# BlueNRG.net
KiCad netlist of a schematic drawn in EAGLE
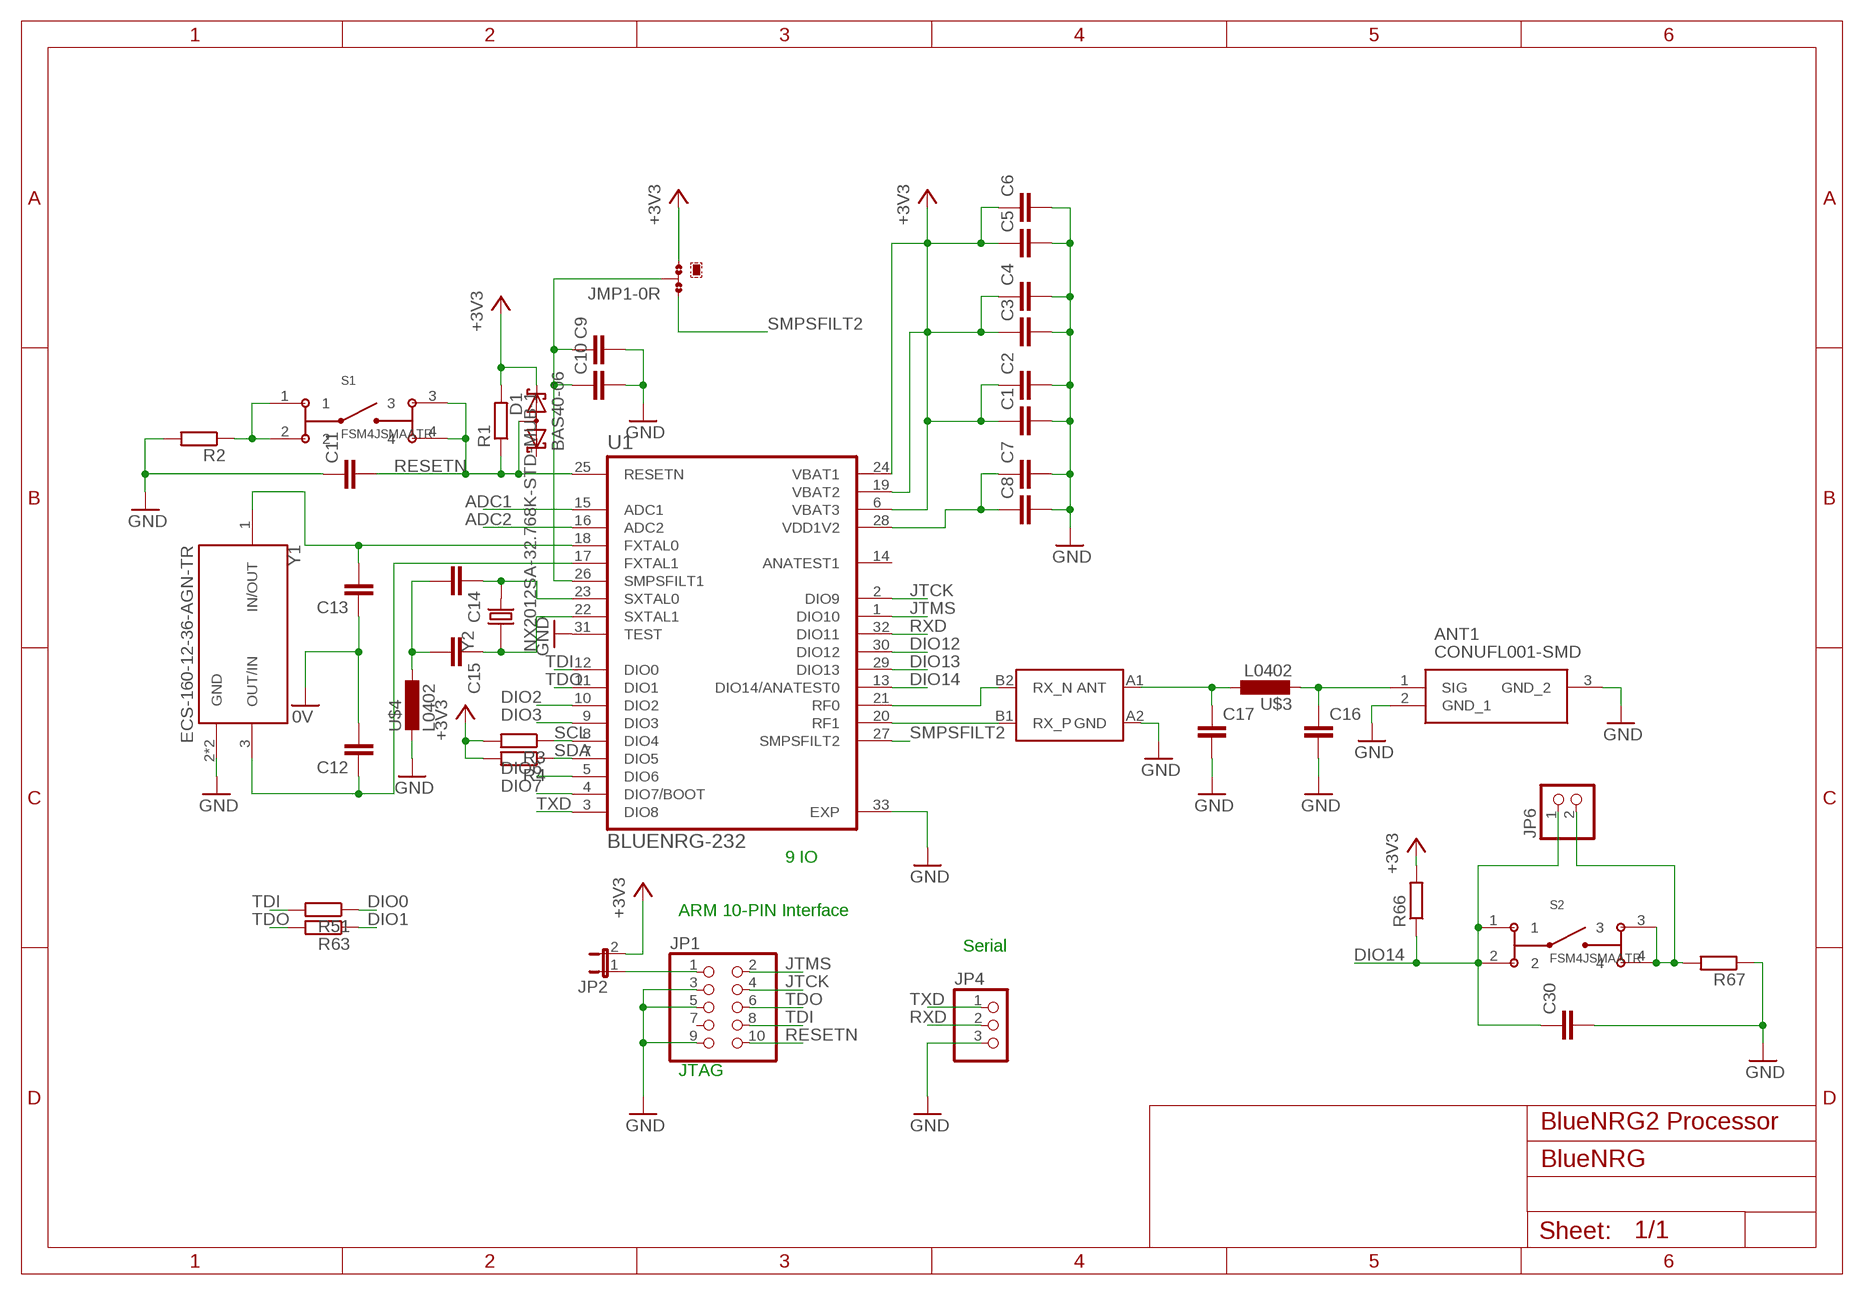
[diagram p0: schematic, sheet 1]

(export (version "E")
  (design (tool "Eeschema 10.0.6"))
  (components
    (comp (ref "ANT1")
      (value "CONUFL001-SMD")
      (footprint "eagle-import:CONUFL001-SMD")
      (fields (field (name "MOUSER_PART_NUMBER") "712-CONUFL001-SMD"))
      (libsource (lib "eagle-import") (part "CONUFL001-SMD"))
    )
    (comp (ref "C1")
      (value "C-EUC0805K")
      (footprint "eagle-import:C0805K")
      (libsource (lib "eagle-import") (part "C-EUC0805K"))
    )
    (comp (ref "C2")
      (value "C-EUC0805K")
      (footprint "eagle-import:C0805K")
      (libsource (lib "eagle-import") (part "C-EUC0805K"))
    )
    (comp (ref "C3")
      (value "C-EUC0805K")
      (footprint "eagle-import:C0805K")
      (libsource (lib "eagle-import") (part "C-EUC0805K"))
    )
    (comp (ref "C4")
      (value "C-EUC0805K")
      (footprint "eagle-import:C0805K")
      (libsource (lib "eagle-import") (part "C-EUC0805K"))
    )
    (comp (ref "C5")
      (value "C-EUC0805K")
      (footprint "eagle-import:C0805K")
      (libsource (lib "eagle-import") (part "C-EUC0805K"))
    )
    (comp (ref "C6")
      (value "C-EUC0805K")
      (footprint "eagle-import:C0805K")
      (libsource (lib "eagle-import") (part "C-EUC0805K"))
    )
    (comp (ref "C7")
      (value "C-EUC0805K")
      (footprint "eagle-import:C0805K")
      (libsource (lib "eagle-import") (part "C-EUC0805K"))
    )
    (comp (ref "C8")
      (value "C-EUC0805K")
      (footprint "eagle-import:C0805K")
      (libsource (lib "eagle-import") (part "C-EUC0805K"))
    )
    (comp (ref "C9")
      (value "C-EUC0805K")
      (footprint "eagle-import:C0805K")
      (libsource (lib "eagle-import") (part "C-EUC0805K"))
    )
    (comp (ref "C10")
      (value "C-EUC0805K")
      (footprint "eagle-import:C0805K")
      (libsource (lib "eagle-import") (part "C-EUC0805K"))
    )
    (comp (ref "C11")
      (value "C-EUC0805")
      (footprint "eagle-import:C0805")
      (libsource (lib "eagle-import") (part "C-EUC0805"))
    )
    (comp (ref "C12")
      (value "C-EUC0805")
      (footprint "eagle-import:C0805")
      (libsource (lib "eagle-import") (part "C-EUC0805"))
    )
    (comp (ref "C13")
      (value "C-EUC0805")
      (footprint "eagle-import:C0805")
      (libsource (lib "eagle-import") (part "C-EUC0805"))
    )
    (comp (ref "C14")
      (value "C-EUC0805")
      (footprint "eagle-import:C0805")
      (libsource (lib "eagle-import") (part "C-EUC0805"))
    )
    (comp (ref "C15")
      (value "C-EUC0805")
      (footprint "eagle-import:C0805")
      (libsource (lib "eagle-import") (part "C-EUC0805"))
    )
    (comp (ref "C16")
      (value "C-EUC0402")
      (footprint "eagle-import:C0402")
      (libsource (lib "eagle-import") (part "C-EUC0402"))
    )
    (comp (ref "C17")
      (value "C-EUC0402")
      (footprint "eagle-import:C0402")
      (libsource (lib "eagle-import") (part "C-EUC0402"))
    )
    (comp (ref "C30")
      (value "C-EUC0805")
      (footprint "eagle-import:C0805")
      (libsource (lib "eagle-import") (part "C-EUC0805"))
    )
    (comp (ref "D1")
      (value "BAS40-06")
      (footprint "eagle-import:SOT23")
      (libsource (lib "eagle-import") (part "BAS40-06"))
    )
    (comp (ref "JMP1")
      (value "0R-JUMPA")
      (footprint "eagle-import:A0R-JMP")
      (libsource (lib "eagle-import") (part "0R-JUMPA"))
    )
    (comp (ref "JP1")
      (value "PINHD-2X5")
      (footprint "eagle-import:2X05")
      (libsource (lib "eagle-import") (part "PINHD-2X5"))
    )
    (comp (ref "JP2")
      (value "JP1E")
      (footprint "eagle-import:JP1")
      (libsource (lib "eagle-import") (part "JP1E"))
    )
    (comp (ref "JP4")
      (value "PINHD-1X3")
      (footprint "eagle-import:1X03")
      (libsource (lib "eagle-import") (part "PINHD-1X3"))
    )
    (comp (ref "JP6")
      (value "PINHD-1X2")
      (footprint "eagle-import:1X02")
      (libsource (lib "eagle-import") (part "PINHD-1X2"))
    )
    (comp (ref "R1")
      (value "R-EU_R0805")
      (footprint "eagle-import:R0805")
      (libsource (lib "eagle-import") (part "R-EU_R0805"))
    )
    (comp (ref "R2")
      (value "R-EU_R0805")
      (footprint "eagle-import:R0805")
      (libsource (lib "eagle-import") (part "R-EU_R0805"))
    )
    (comp (ref "R3")
      (value "R-EU_R0805")
      (footprint "eagle-import:R0805")
      (libsource (lib "eagle-import") (part "R-EU_R0805"))
    )
    (comp (ref "R4")
      (value "R-EU_R0805")
      (footprint "eagle-import:R0805")
      (libsource (lib "eagle-import") (part "R-EU_R0805"))
    )
    (comp (ref "R51")
      (value "R-EU_R0805")
      (footprint "eagle-import:R0805")
      (libsource (lib "eagle-import") (part "R-EU_R0805"))
    )
    (comp (ref "R63")
      (value "R-EU_R0805")
      (footprint "eagle-import:R0805")
      (libsource (lib "eagle-import") (part "R-EU_R0805"))
    )
    (comp (ref "R66")
      (value "R-EU_R1210")
      (footprint "eagle-import:R1210")
      (libsource (lib "eagle-import") (part "R-EU_R1210"))
    )
    (comp (ref "R67")
      (value "R-EU_R1210")
      (footprint "eagle-import:R1210")
      (libsource (lib "eagle-import") (part "R-EU_R1210"))
    )
    (comp (ref "S1")
      (value "FSM4JSMAATR")
      (footprint "eagle-import:SW_FSM4JSMAATR")
      (fields (field (name "MF") "TE Connectivity"))
      (libsource (lib "eagle-import") (part "FSM4JSMAATR"))
    )
    (comp (ref "S2")
      (value "FSM4JSMAATR")
      (footprint "eagle-import:SW_FSM4JSMAATR")
      (fields (field (name "MF") "TE Connectivity"))
      (libsource (lib "eagle-import") (part "FSM4JSMAATR"))
    )
    (comp (ref "U$3")
      (value "L0402")
      (footprint "eagle-import:R0402")
      (libsource (lib "eagle-import") (part "L0402"))
    )
    (comp (ref "U$4")
      (value "L0402")
      (footprint "eagle-import:R0402")
      (libsource (lib "eagle-import") (part "L0402"))
    )
    (comp (ref "U$5")
      (value "BALF-NRG-01D3")
      (footprint "eagle-import:FLIPCHIP")
      (fields (field (name "MF") "STMicroelectronics"))
      (libsource (lib "eagle-import") (part "BALF-NRG-01D3"))
    )
    (comp (ref "U1")
      (value "BLUENRG-232")
      (footprint "eagle-import:QFN50P500X500X100-33T345N")
      (fields (field (name "MF") "STMicroelectronics"))
      (libsource (lib "eagle-import") (part "BLUENRG-232"))
    )
    (comp (ref "Y1")
      (value "ECS-160-12-36-AGN-TR")
      (footprint "eagle-import:XTAL_ECS-160-12-36-AGN-TR")
      (fields (field (name "MF") "ECS Inc."))
      (libsource (lib "eagle-import") (part "ECS-160-12-36-AGN-TR"))
    )
    (comp (ref "Y2")
      (value "NX2012SA-32.768K-STD-MUB-1")
      (footprint "eagle-import:XTAL_NX2012SA-32.768K-STD-MUB-1")
      (fields (field (name "MF") "NDK America,"))
      (libsource (lib "eagle-import") (part "NX2012SA-32.768K-STD-MUB-1"))
    )
  )
  (nets
    (net (code "1") (name "+3V3") (class "Default")
      (node (ref "C1") (pin "1") (pinfunction "1_1") (pintype "passive"))
      (node (ref "C2") (pin "1") (pinfunction "1_1") (pintype "passive"))
      (node (ref "C3") (pin "1") (pinfunction "1_1") (pintype "passive"))
      (node (ref "C4") (pin "1") (pinfunction "1_1") (pintype "passive"))
      (node (ref "C5") (pin "1") (pinfunction "1_1") (pintype "passive"))
      (node (ref "C6") (pin "1") (pinfunction "1_1") (pintype "passive"))
      (node (ref "D1") (pin "2") (pinfunction "K2_2") (pintype "passive"))
      (node (ref "JMP1") (pin "3") (pinfunction "3_3") (pintype "passive"))
      (node (ref "JP2") (pin "2") (pinfunction "2_2") (pintype "passive"))
      (node (ref "R1") (pin "2") (pinfunction "2_2") (pintype "passive"))
      (node (ref "R3") (pin "2") (pinfunction "2_2") (pintype "passive"))
      (node (ref "R4") (pin "2") (pinfunction "2_2") (pintype "passive"))
      (node (ref "R66") (pin "2") (pinfunction "2_2") (pintype "passive"))
      (node (ref "U1") (pin "19") (pinfunction "VBAT2_19") (pintype "power_in"))
      (node (ref "U1") (pin "24") (pinfunction "VBAT1_24") (pintype "power_in"))
      (node (ref "U1") (pin "6") (pinfunction "VBAT3_6") (pintype "power_in"))
    )
    (net (code "2") (name "/ADC1") (class "Default")
      (node (ref "U1") (pin "15") (pinfunction "ADC1_15") (pintype "input"))
    )
    (net (code "3") (name "/ADC2") (class "Default")
      (node (ref "U1") (pin "16") (pinfunction "ADC2_16") (pintype "input"))
    )
    (net (code "4") (name "/DIO0") (class "Default")
      (node (ref "R51") (pin "1") (pinfunction "1_1") (pintype "passive"))
    )
    (net (code "5") (name "/DIO1") (class "Default")
      (node (ref "R63") (pin "1") (pinfunction "1_1") (pintype "passive"))
    )
    (net (code "6") (name "/DIO2") (class "Default")
      (node (ref "U1") (pin "10") (pinfunction "DIO2_10") (pintype "bidirectional"))
    )
    (net (code "7") (name "/DIO3") (class "Default")
      (node (ref "U1") (pin "9") (pinfunction "DIO3_9") (pintype "bidirectional"))
    )
    (net (code "8") (name "/DIO6") (class "Default")
      (node (ref "U1") (pin "5") (pinfunction "DIO6_5") (pintype "bidirectional"))
    )
    (net (code "9") (name "/DIO7") (class "Default")
      (node (ref "U1") (pin "4") (pinfunction "DIO7/BOOT_4") (pintype "bidirectional"))
    )
    (net (code "10") (name "/DIO12") (class "Default")
      (node (ref "U1") (pin "30") (pinfunction "DIO12_30") (pintype "bidirectional"))
    )
    (net (code "11") (name "/DIO13") (class "Default")
      (node (ref "U1") (pin "29") (pinfunction "DIO13_29") (pintype "bidirectional"))
    )
    (net (code "12") (name "/DIO14") (class "Default")
      (node (ref "C30") (pin "1") (pinfunction "1_1") (pintype "passive"))
      (node (ref "JP6") (pin "1") (pinfunction "1_1") (pintype "passive"))
      (node (ref "R66") (pin "1") (pinfunction "1_1") (pintype "passive"))
      (node (ref "S2") (pin "1") (pinfunction "1_1") (pintype "passive"))
      (node (ref "S2") (pin "2") (pinfunction "2_2") (pintype "passive"))
      (node (ref "U1") (pin "13") (pinfunction "DIO14/ANATEST0_13") (pintype "bidirectional"))
    )
    (net (code "13") (name "/JTCK") (class "Default")
      (node (ref "JP1") (pin "4") (pinfunction "4_4") (pintype "passive"))
      (node (ref "U1") (pin "2") (pinfunction "DIO9_2") (pintype "bidirectional"))
    )
    (net (code "14") (name "/JTMS") (class "Default")
      (node (ref "JP1") (pin "2") (pinfunction "2_2") (pintype "passive"))
      (node (ref "U1") (pin "1") (pinfunction "DIO10_1") (pintype "bidirectional"))
    )
    (net (code "15") (name "/RESETN") (class "Default")
      (node (ref "C11") (pin "2") (pinfunction "2_2") (pintype "passive"))
      (node (ref "D1") (pin "3") (pinfunction "AA_3") (pintype "passive"))
      (node (ref "JP1") (pin "10") (pinfunction "10_10") (pintype "passive"))
      (node (ref "R1") (pin "1") (pinfunction "1_1") (pintype "passive"))
      (node (ref "S1") (pin "3") (pinfunction "3_3") (pintype "passive"))
      (node (ref "S1") (pin "4") (pinfunction "4_4") (pintype "passive"))
      (node (ref "U1") (pin "25") (pinfunction "RESETN_25") (pintype "input"))
    )
    (net (code "16") (name "/RXD") (class "Default")
      (node (ref "JP4") (pin "2") (pinfunction "2_2") (pintype "passive"))
      (node (ref "U1") (pin "32") (pinfunction "DIO11_32") (pintype "bidirectional"))
    )
    (net (code "17") (name "/SCL") (class "Default")
      (node (ref "R3") (pin "1") (pinfunction "1_1") (pintype "passive"))
      (node (ref "U1") (pin "8") (pinfunction "DIO4_8") (pintype "bidirectional"))
    )
    (net (code "18") (name "/SDA") (class "Default")
      (node (ref "R4") (pin "1") (pinfunction "1_1") (pintype "passive"))
      (node (ref "U1") (pin "7") (pinfunction "DIO5_7") (pintype "bidirectional"))
    )
    (net (code "19") (name "/SMPSFILT2") (class "Default")
      (node (ref "JMP1") (pin "1") (pinfunction "1_1") (pintype "passive"))
      (node (ref "U1") (pin "27") (pinfunction "SMPSFILT2_27") (pintype "bidirectional"))
    )
    (net (code "20") (name "/TDI") (class "Default")
      (node (ref "JP1") (pin "8") (pinfunction "8_8") (pintype "passive"))
      (node (ref "R51") (pin "2") (pinfunction "2_2") (pintype "passive"))
      (node (ref "U1") (pin "12") (pinfunction "DIO0_12") (pintype "bidirectional"))
    )
    (net (code "21") (name "/TDO") (class "Default")
      (node (ref "JP1") (pin "6") (pinfunction "6_6") (pintype "passive"))
      (node (ref "R63") (pin "2") (pinfunction "2_2") (pintype "passive"))
      (node (ref "U1") (pin "11") (pinfunction "DIO1_11") (pintype "bidirectional"))
    )
    (net (code "22") (name "/TXD") (class "Default")
      (node (ref "JP4") (pin "1") (pinfunction "1_1") (pintype "passive"))
      (node (ref "U1") (pin "3") (pinfunction "DIO8_3") (pintype "bidirectional"))
    )
    (net (code "23") (name "0V") (class "Default")
      (node (ref "C12") (pin "2") (pinfunction "2_2") (pintype "passive"))
      (node (ref "C13") (pin "1") (pinfunction "1_1") (pintype "passive"))
    )
    (net (code "24") (name "GND") (class "Default")
      (node (ref "ANT1") (pin "2") (pinfunction "GND_1_2") (pintype "bidirectional"))
      (node (ref "ANT1") (pin "3") (pinfunction "GND_2_3") (pintype "bidirectional"))
      (node (ref "C1") (pin "2") (pinfunction "2_2") (pintype "passive"))
      (node (ref "C10") (pin "2") (pinfunction "2_2") (pintype "passive"))
      (node (ref "C11") (pin "1") (pinfunction "1_1") (pintype "passive"))
      (node (ref "C16") (pin "2") (pinfunction "2_2") (pintype "passive"))
      (node (ref "C17") (pin "2") (pinfunction "2_2") (pintype "passive"))
      (node (ref "C2") (pin "2") (pinfunction "2_2") (pintype "passive"))
      (node (ref "C3") (pin "2") (pinfunction "2_2") (pintype "passive"))
      (node (ref "C30") (pin "2") (pinfunction "2_2") (pintype "passive"))
      (node (ref "C4") (pin "2") (pinfunction "2_2") (pintype "passive"))
      (node (ref "C5") (pin "2") (pinfunction "2_2") (pintype "passive"))
      (node (ref "C6") (pin "2") (pinfunction "2_2") (pintype "passive"))
      (node (ref "C7") (pin "2") (pinfunction "2_2") (pintype "passive"))
      (node (ref "C8") (pin "2") (pinfunction "2_2") (pintype "passive"))
      (node (ref "C9") (pin "2") (pinfunction "2_2") (pintype "passive"))
      (node (ref "JP1") (pin "3") (pinfunction "3_3") (pintype "passive"))
      (node (ref "JP1") (pin "5") (pinfunction "5_5") (pintype "passive"))
      (node (ref "JP1") (pin "9") (pinfunction "9_9") (pintype "passive"))
      (node (ref "JP4") (pin "3") (pinfunction "3_3") (pintype "passive"))
      (node (ref "R2") (pin "2") (pinfunction "2_2") (pintype "passive"))
      (node (ref "R67") (pin "1") (pinfunction "1_1") (pintype "passive"))
      (node (ref "U$4") (pin "2") (pinfunction "2_2") (pintype "passive"))
      (node (ref "U$5") (pin "A2") (pinfunction "GND_A2") (pintype "power_in"))
      (node (ref "U1") (pin "31") (pinfunction "TEST_31") (pintype "input"))
      (node (ref "U1") (pin "33") (pinfunction "EXP_33") (pintype "power_in"))
      (node (ref "Y1") (pin "2") (pinfunction "GND_2") (pintype "power_in"))
      (node (ref "Y1") (pin "4") (pinfunction "GND_4") (pintype "power_in"))
    )
    (net (code "25") (name "Net-(ANT1-SIG)") (class "Default")
      (node (ref "ANT1") (pin "1") (pinfunction "SIG_1") (pintype "input"))
      (node (ref "C16") (pin "1") (pinfunction "1_1") (pintype "passive"))
      (node (ref "U$3") (pin "2") (pinfunction "2_2") (pintype "passive"))
    )
    (net (code "26") (name "Net-(C14-Pad2)") (class "Default")
      (node (ref "C14") (pin "2") (pinfunction "2_2") (pintype "passive"))
      (node (ref "C15") (pin "2") (pinfunction "2_2") (pintype "passive"))
      (node (ref "U$4") (pin "1") (pinfunction "1_1") (pintype "passive"))
    )
    (net (code "27") (name "Net-(JP1-Pad1)") (class "Default")
      (node (ref "JP1") (pin "1") (pinfunction "1_1") (pintype "passive"))
      (node (ref "JP2") (pin "1") (pinfunction "1_1") (pintype "passive"))
    )
    (net (code "28") (name "Net-(JP6-Pad2)") (class "Default")
      (node (ref "JP6") (pin "2") (pinfunction "2_2") (pintype "passive"))
      (node (ref "R67") (pin "2") (pinfunction "2_2") (pintype "passive"))
      (node (ref "S2") (pin "3") (pinfunction "3_3") (pintype "passive"))
      (node (ref "S2") (pin "4") (pinfunction "4_4") (pintype "passive"))
    )
    (net (code "29") (name "Net-(R2-Pad1)") (class "Default")
      (node (ref "R2") (pin "1") (pinfunction "1_1") (pintype "passive"))
      (node (ref "S1") (pin "1") (pinfunction "1_1") (pintype "passive"))
      (node (ref "S1") (pin "2") (pinfunction "2_2") (pintype "passive"))
    )
    (net (code "30") (name "Net-(U$5-ANT)") (class "Default")
      (node (ref "C17") (pin "1") (pinfunction "1_1") (pintype "passive"))
      (node (ref "U$3") (pin "1") (pinfunction "1_1") (pintype "passive"))
      (node (ref "U$5") (pin "A1") (pinfunction "ANT_A1") (pintype "power_in"))
    )
    (net (code "31") (name "Net-(U$5-RX_N)") (class "Default")
      (node (ref "U$5") (pin "B2") (pinfunction "RX_N_B2") (pintype "power_in"))
      (node (ref "U1") (pin "21") (pinfunction "RF0_21") (pintype "bidirectional"))
    )
    (net (code "32") (name "Net-(U$5-RX_P)") (class "Default")
      (node (ref "U$5") (pin "B1") (pinfunction "RX_P_B1") (pintype "power_in"))
      (node (ref "U1") (pin "20") (pinfunction "RF1_20") (pintype "bidirectional"))
    )
    (net (code "33") (name "Net-(U1-FXTAL0)") (class "Default")
      (node (ref "C13") (pin "2") (pinfunction "2_2") (pintype "passive"))
      (node (ref "U1") (pin "18") (pinfunction "FXTAL0_18") (pintype "input"))
      (node (ref "Y1") (pin "1") (pinfunction "IN/OUT_1") (pintype "bidirectional"))
    )
    (net (code "34") (name "Net-(U1-FXTAL1)") (class "Default")
      (node (ref "C12") (pin "1") (pinfunction "1_1") (pintype "passive"))
      (node (ref "U1") (pin "17") (pinfunction "FXTAL1_17") (pintype "input"))
      (node (ref "Y1") (pin "3") (pinfunction "OUT/IN_3") (pintype "bidirectional"))
    )
    (net (code "35") (name "Net-(U1-SMPSFILT1)") (class "Default")
      (node (ref "C10") (pin "1") (pinfunction "1_1") (pintype "passive"))
      (node (ref "C9") (pin "1") (pinfunction "1_1") (pintype "passive"))
      (node (ref "JMP1") (pin "2") (pinfunction "2_2") (pintype "passive"))
      (node (ref "U1") (pin "26") (pinfunction "SMPSFILT1_26") (pintype "input"))
    )
    (net (code "36") (name "Net-(U1-SXTAL0)") (class "Default")
      (node (ref "C14") (pin "1") (pinfunction "1_1") (pintype "passive"))
      (node (ref "U1") (pin "23") (pinfunction "SXTAL0_23") (pintype "input"))
      (node (ref "Y2") (pin "2") (pinfunction "2_2") (pintype "passive"))
    )
    (net (code "37") (name "Net-(U1-SXTAL1)") (class "Default")
      (node (ref "C15") (pin "1") (pinfunction "1_1") (pintype "passive"))
      (node (ref "U1") (pin "22") (pinfunction "SXTAL1_22") (pintype "input"))
      (node (ref "Y2") (pin "1") (pinfunction "1_1") (pintype "passive"))
    )
    (net (code "38") (name "Net-(U1-VDD1V2)") (class "Default")
      (node (ref "C7") (pin "1") (pinfunction "1_1") (pintype "passive"))
      (node (ref "C8") (pin "1") (pinfunction "1_1") (pintype "passive"))
      (node (ref "U1") (pin "28") (pinfunction "VDD1V2_28") (pintype "power_in"))
    )
    (net (code "39") (name "unconnected-(D1-K1-Pad1)") (class "Default")
      (node (ref "D1") (pin "1") (pinfunction "K1_1") (pintype "passive"))
    )
    (net (code "40") (name "unconnected-(JP1-Pad7)") (class "Default")
      (node (ref "JP1") (pin "7") (pinfunction "7_7") (pintype "passive"))
    )
    (net (code "41") (name "unconnected-(U1-ANATEST1-Pad14)") (class "Default")
      (node (ref "U1") (pin "14") (pinfunction "ANATEST1_14") (pintype "output"))
    )
  )
)
